# Adafruit_PowerBoost_1000C.net
KiCad netlist of a schematic drawn in EAGLE
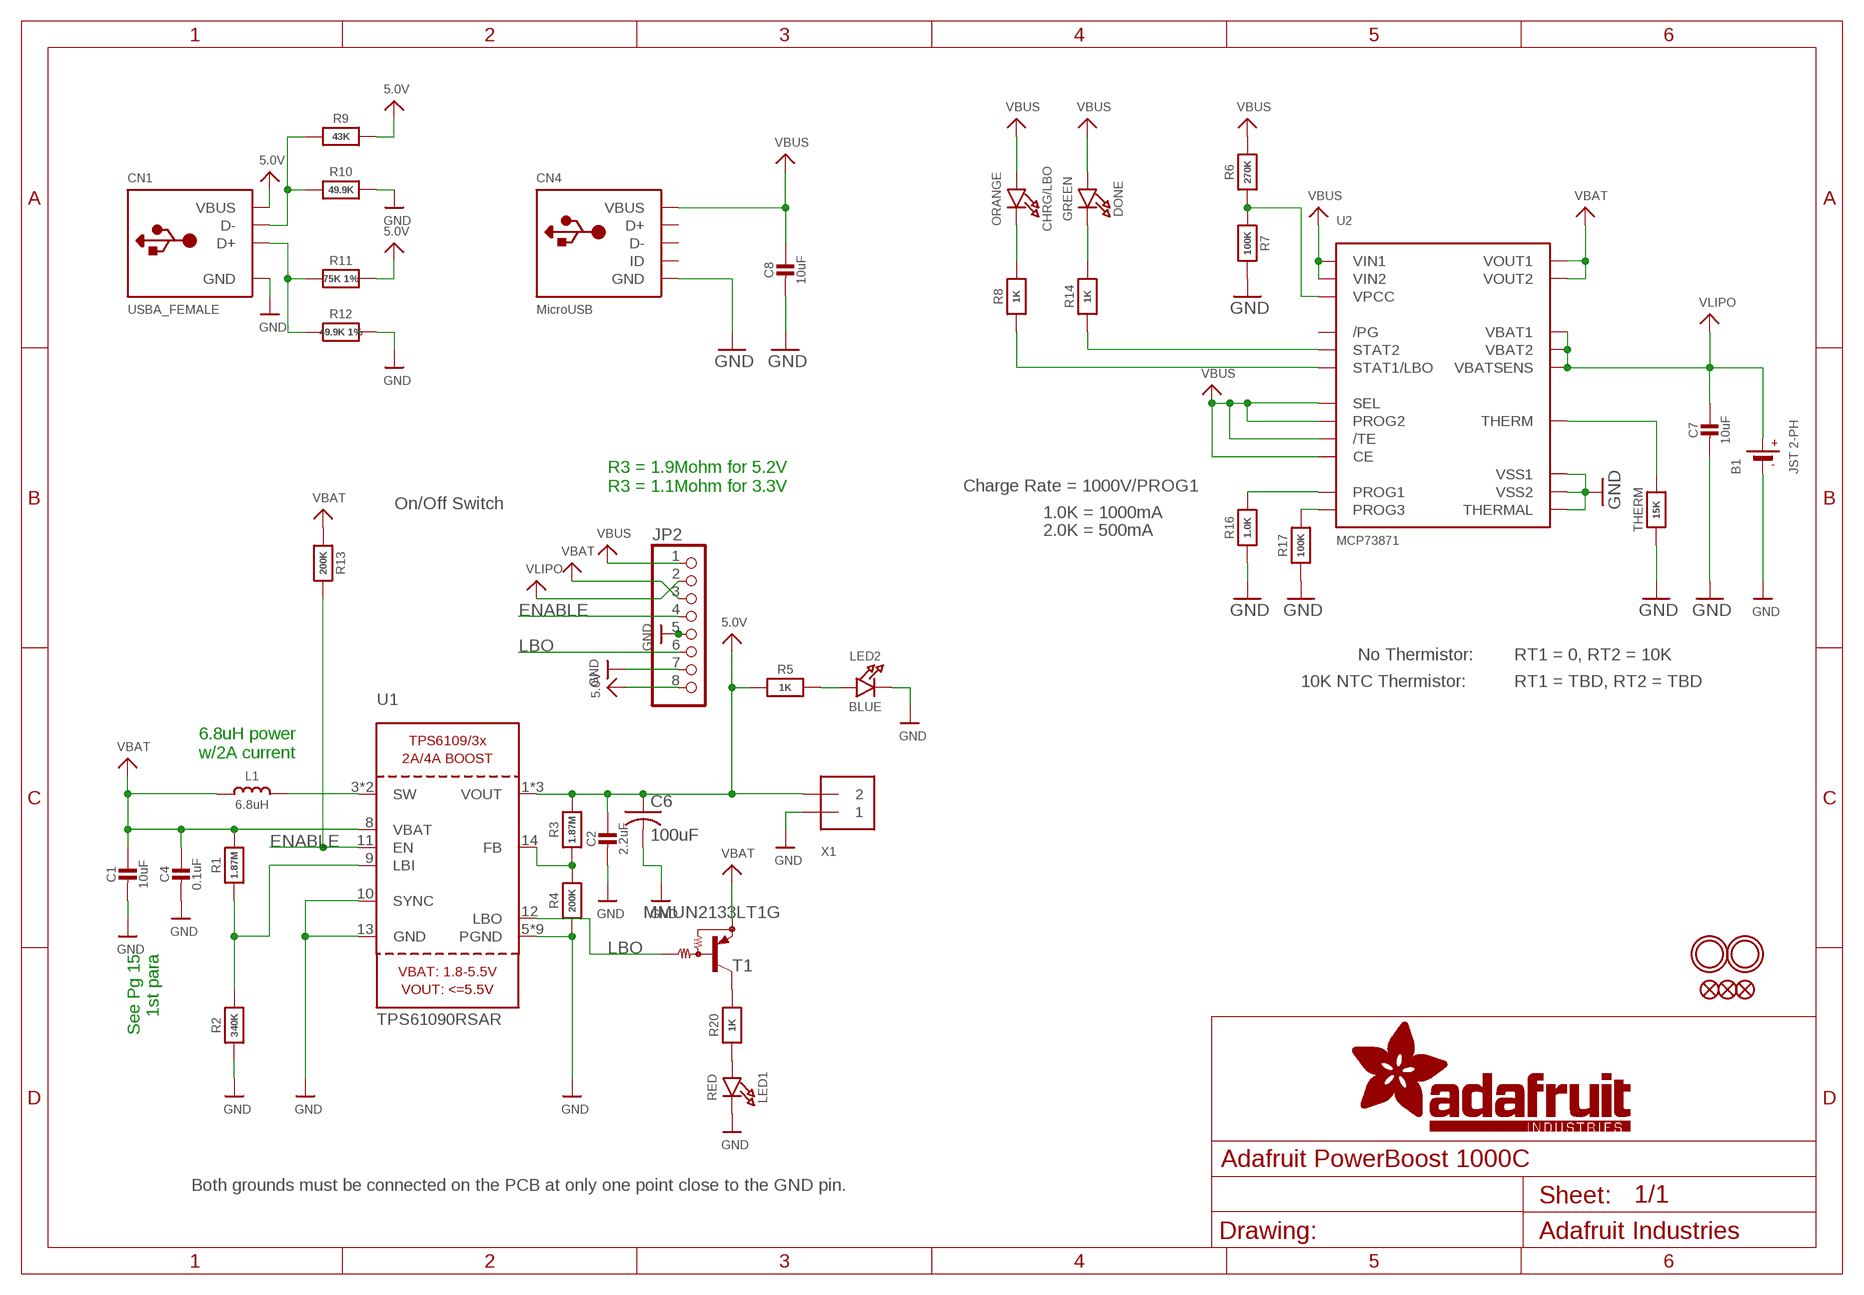
[diagram p0: schematic, sheet 1]

(export (version "E")
  (design (tool "Eeschema 10.0.6"))
  (components
    (comp (ref "B1")
      (value "JST 2-PH")
      (footprint "eagle-import:JSTPH2")
      (libsource (lib "eagle-import") (part "BATTERY"))
    )
    (comp (ref "C1")
      (value "10uF")
      (footprint "eagle-import:0805-NO")
      (libsource (lib "eagle-import") (part "CAP_CERAMIC0805-NOOUTLINE"))
    )
    (comp (ref "C2")
      (value "2.2uF")
      (footprint "eagle-import:0805-NO")
      (libsource (lib "eagle-import") (part "CAP_CERAMIC0805-NOOUTLINE"))
    )
    (comp (ref "C4")
      (value "0.1uF")
      (footprint "eagle-import:0805_10MGAP")
      (libsource (lib "eagle-import") (part "CAP_CERAMIC0805_10MGAP"))
    )
    (comp (ref "C6")
      (value "100uF")
      (footprint "eagle-import:C1210")
      (libsource (lib "eagle-import") (part "C-USC1210"))
    )
    (comp (ref "C7")
      (value "10uF")
      (footprint "eagle-import:0805-NO")
      (libsource (lib "eagle-import") (part "CAP_CERAMIC0805-NOOUTLINE"))
    )
    (comp (ref "C8")
      (value "10uF")
      (footprint "eagle-import:0805-NO")
      (libsource (lib "eagle-import") (part "CAP_CERAMIC0805-NOOUTLINE"))
    )
    (comp (ref "CHRG/LBO")
      (value "ORANGE")
      (footprint "eagle-import:CHIPLED_0805_NOOUTLINE")
      (libsource (lib "eagle-import") (part "LED0805_NOOUTLINE"))
    )
    (comp (ref "CN1")
      (value "USBA_FEMALE")
      (footprint "eagle-import:USB_HOST-PTH")
      (libsource (lib "eagle-import") (part "USB_TYPEAPTHFML"))
    )
    (comp (ref "CN4")
      (value "MicroUSB")
      (footprint "eagle-import:4UCONN_20329")
      (libsource (lib "eagle-import") (part "USBMICRO_20329"))
    )
    (comp (ref "DONE")
      (value "GREEN")
      (footprint "eagle-import:CHIPLED_0805_NOOUTLINE")
      (libsource (lib "eagle-import") (part "LED0805_NOOUTLINE"))
    )
    (comp (ref "FID1")
      (value "FIDUCIAL\"\"")
      (footprint "eagle-import:FIDUCIAL_1MM")
      (fields (field (name "BOM") "EXCLUDE"))
      (libsource (lib "eagle-import") (part "FIDUCIAL{dblquote}{dblquote}"))
    )
    (comp (ref "FID2")
      (value "FIDUCIAL\"\"")
      (footprint "eagle-import:FIDUCIAL_1MM")
      (libsource (lib "eagle-import") (part "FIDUCIAL{dblquote}{dblquote}"))
    )
    (comp (ref "FID3")
      (value "FIDUCIAL\"\"")
      (footprint "eagle-import:FIDUCIAL_1MM")
      (fields (field (name "BOM") "EXCLUDE"))
      (libsource (lib "eagle-import") (part "FIDUCIAL{dblquote}{dblquote}"))
    )
    (comp (ref "JP2")
      (value "HEADER-1X8ROUND")
      (footprint "eagle-import:1X08_ROUND")
      (libsource (lib "eagle-import") (part "HEADER-1X8ROUND"))
    )
    (comp (ref "L1")
      (value "6.8uH")
      (footprint "eagle-import:INDUCTOR_5X5MM_TDK_VLC5045")
      (libsource (lib "eagle-import") (part "INDUCTORTDK_VLC5045"))
    )
    (comp (ref "LED1")
      (value "RED")
      (footprint "eagle-import:CHIPLED_0805_NOOUTLINE")
      (libsource (lib "eagle-import") (part "LED0805_NOOUTLINE"))
    )
    (comp (ref "LED2")
      (value "BLUE")
      (footprint "eagle-import:CHIPLED_0805_NOOUTLINE")
      (libsource (lib "eagle-import") (part "LED0805_NOOUTLINE"))
    )
    (comp (ref "R1")
      (value "1.87M")
      (footprint "eagle-import:_0805MP")
      (libsource (lib "eagle-import") (part "RESISTOR_0805MP"))
    )
    (comp (ref "R2")
      (value "340K")
      (footprint "eagle-import:_0805MP")
      (libsource (lib "eagle-import") (part "RESISTOR_0805MP"))
    )
    (comp (ref "R3")
      (value "1.87M")
      (footprint "eagle-import:0805-NO")
      (libsource (lib "eagle-import") (part "RESISTOR0805_NOOUTLINE"))
    )
    (comp (ref "R4")
      (value "200K")
      (footprint "eagle-import:0805-NO")
      (libsource (lib "eagle-import") (part "RESISTOR0805_NOOUTLINE"))
    )
    (comp (ref "R5")
      (value "1K")
      (footprint "eagle-import:0805-NO")
      (libsource (lib "eagle-import") (part "RESISTOR0805_NOOUTLINE"))
    )
    (comp (ref "R6")
      (value "270K")
      (footprint "eagle-import:0805-NO")
      (libsource (lib "eagle-import") (part "RESISTOR0805_NOOUTLINE"))
    )
    (comp (ref "R7")
      (value "100K")
      (footprint "eagle-import:0805-NO")
      (libsource (lib "eagle-import") (part "RESISTOR0805_NOOUTLINE"))
    )
    (comp (ref "R8")
      (value "1K")
      (footprint "eagle-import:0805-NO")
      (libsource (lib "eagle-import") (part "RESISTOR0805_NOOUTLINE"))
    )
    (comp (ref "R9")
      (value "43K")
      (footprint "eagle-import:0805-NO")
      (libsource (lib "eagle-import") (part "RESISTOR0805_NOOUTLINE"))
    )
    (comp (ref "R10")
      (value "49.9K")
      (footprint "eagle-import:0805-NO")
      (libsource (lib "eagle-import") (part "RESISTOR0805_NOOUTLINE"))
    )
    (comp (ref "R11")
      (value "75K 1%")
      (footprint "eagle-import:0805-NO")
      (libsource (lib "eagle-import") (part "RESISTOR0805_NOOUTLINE"))
    )
    (comp (ref "R12")
      (value "49.9K 1%")
      (footprint "eagle-import:0805-NO")
      (libsource (lib "eagle-import") (part "RESISTOR0805_NOOUTLINE"))
    )
    (comp (ref "R13")
      (value "200K")
      (footprint "eagle-import:0805-NO")
      (libsource (lib "eagle-import") (part "RESISTOR0805_NOOUTLINE"))
    )
    (comp (ref "R14")
      (value "1K")
      (footprint "eagle-import:0805-NO")
      (libsource (lib "eagle-import") (part "RESISTOR0805_NOOUTLINE"))
    )
    (comp (ref "R16")
      (value "1.0K")
      (footprint "eagle-import:0805-NO")
      (libsource (lib "eagle-import") (part "RESISTOR0805_NOOUTLINE"))
    )
    (comp (ref "R17")
      (value "100K")
      (footprint "eagle-import:0805-NO")
      (libsource (lib "eagle-import") (part "RESISTOR0805_NOOUTLINE"))
    )
    (comp (ref "R20")
      (value "1K")
      (footprint "eagle-import:0805-NO")
      (libsource (lib "eagle-import") (part "RESISTOR0805_NOOUTLINE"))
    )
    (comp (ref "T1")
      (value "MMUN2133LT1G")
      (footprint "eagle-import:SC59-BEC")
      (libsource (lib "eagle-import") (part "-PNP_DRIVER-SC59-BECMUN2114T1"))
    )
    (comp (ref "THERM")
      (value "15K")
      (footprint "eagle-import:0805-NO")
      (libsource (lib "eagle-import") (part "RESISTOR0805_NOOUTLINE"))
    )
    (comp (ref "U$10")
      (value "MOUNTINGHOLE2.5")
      (footprint "eagle-import:MOUNTINGHOLE_2.5_PLATED")
      (libsource (lib "eagle-import") (part "MOUNTINGHOLE2.5"))
    )
    (comp (ref "U$11")
      (value "MOUNTINGHOLE2.5")
      (footprint "eagle-import:MOUNTINGHOLE_2.5_PLATED")
      (libsource (lib "eagle-import") (part "MOUNTINGHOLE2.5"))
    )
    (comp (ref "U1")
      (value "TPS61090RSAR")
      (footprint "eagle-import:PVQFN-16")
      (libsource (lib "eagle-import") (part "VREG_TPS6103X"))
    )
    (comp (ref "U2")
      (value "MCP73871")
      (footprint "eagle-import:QFN20_4MM")
      (libsource (lib "eagle-import") (part "MCP73871"))
    )
    (comp (ref "X1")
      (value "TERMBLOCK_1X2")
      (footprint "eagle-import:TERMBLOCK_1X2-3.5MM")
      (libsource (lib "eagle-import") (part "TERMBLOCK_1X2"))
    )
  )
  (nets
    (net (code "1") (name "/ENABLE") (class "Default")
      (node (ref "JP2") (pin "4") (pinfunction "4_4") (pintype "passive"))
      (node (ref "R13") (pin "2") (pinfunction "2_2") (pintype "passive"))
      (node (ref "U1") (pin "11") (pinfunction "EN_11") (pintype "input"))
    )
    (net (code "2") (name "/LBO") (class "Default")
      (node (ref "JP2") (pin "6") (pinfunction "6_6") (pintype "passive"))
      (node (ref "T1") (pin "B") (pinfunction "B_B") (pintype "passive"))
      (node (ref "U1") (pin "12") (pinfunction "LBO_12") (pintype "output"))
    )
    (net (code "3") (name "5.0V") (class "Default")
      (node (ref "C2") (pin "1") (pinfunction "1_1") (pintype "passive"))
      (node (ref "C6") (pin "1") (pinfunction "1_1") (pintype "passive"))
      (node (ref "CN1") (pin "VBUS") (pinfunction "VBUS_VBUS") (pintype "power_in"))
      (node (ref "JP2") (pin "8") (pinfunction "8_8") (pintype "passive"))
      (node (ref "R11") (pin "2") (pinfunction "2_2") (pintype "passive"))
      (node (ref "R3") (pin "2") (pinfunction "2_2") (pintype "passive"))
      (node (ref "R5") (pin "1") (pinfunction "1_1") (pintype "passive"))
      (node (ref "R9") (pin "2") (pinfunction "2_2") (pintype "passive"))
      (node (ref "U1") (pin "1") (pinfunction "VOUT_1") (pintype "power_in"))
      (node (ref "U1") (pin "15") (pinfunction "VOUT_15") (pintype "power_in"))
      (node (ref "U1") (pin "16") (pinfunction "VOUT_16") (pintype "power_in"))
      (node (ref "X1") (pin "2") (pinfunction "2_2") (pintype "passive"))
    )
    (net (code "4") (name "GND") (class "Default")
      (node (ref "B1") (pin "1") (pinfunction "-_1") (pintype "passive"))
      (node (ref "C1") (pin "2") (pinfunction "2_2") (pintype "passive"))
      (node (ref "C2") (pin "2") (pinfunction "2_2") (pintype "passive"))
      (node (ref "C4") (pin "2") (pinfunction "2_2") (pintype "passive"))
      (node (ref "C6") (pin "2") (pinfunction "2_2") (pintype "passive"))
      (node (ref "C7") (pin "2") (pinfunction "2_2") (pintype "passive"))
      (node (ref "C8") (pin "2") (pinfunction "2_2") (pintype "passive"))
      (node (ref "CN1") (pin "GND") (pinfunction "GND_GND") (pintype "power_in"))
      (node (ref "CN4") (pin "BASE@1") (pinfunction "GND_BASE@1") (pintype "power_in"))
      (node (ref "CN4") (pin "BASE@2") (pinfunction "GND_BASE@2") (pintype "power_in"))
      (node (ref "CN4") (pin "GND") (pinfunction "GND_GND") (pintype "power_in"))
      (node (ref "CN4") (pin "SPRT@1") (pinfunction "GND_SPRT@1") (pintype "power_in"))
      (node (ref "CN4") (pin "SPRT@2") (pinfunction "GND_SPRT@2") (pintype "power_in"))
      (node (ref "CN4") (pin "SPRT@3") (pinfunction "GND_SPRT@3") (pintype "power_in"))
      (node (ref "CN4") (pin "SPRT@4") (pinfunction "GND_SPRT@4") (pintype "power_in"))
      (node (ref "JP2") (pin "5") (pinfunction "5_5") (pintype "passive"))
      (node (ref "JP2") (pin "7") (pinfunction "7_7") (pintype "passive"))
      (node (ref "LED1") (pin "C") (pinfunction "C_C") (pintype "passive"))
      (node (ref "LED2") (pin "C") (pinfunction "C_C") (pintype "passive"))
      (node (ref "R10") (pin "2") (pinfunction "2_2") (pintype "passive"))
      (node (ref "R12") (pin "2") (pinfunction "2_2") (pintype "passive"))
      (node (ref "R16") (pin "1") (pinfunction "1_1") (pintype "passive"))
      (node (ref "R17") (pin "1") (pinfunction "1_1") (pintype "passive"))
      (node (ref "R2") (pin "1") (pinfunction "1_1") (pintype "passive"))
      (node (ref "R4") (pin "1") (pinfunction "1_1") (pintype "passive"))
      (node (ref "R7") (pin "2") (pinfunction "2_2") (pintype "passive"))
      (node (ref "THERM") (pin "1") (pinfunction "1_1") (pintype "passive"))
      (node (ref "U1") (pin "10") (pinfunction "SYNC_10") (pintype "input"))
      (node (ref "U1") (pin "13") (pinfunction "GND_13") (pintype "power_in"))
      (node (ref "U1") (pin "5") (pinfunction "PGND_5") (pintype "power_in"))
      (node (ref "U1") (pin "6") (pinfunction "PGND_6") (pintype "power_in"))
      (node (ref "U1") (pin "7") (pinfunction "PGND_7") (pintype "power_in"))
      (node (ref "U1") (pin "P$18") (pinfunction "PGND_P$18") (pintype "power_in"))
      (node (ref "U1") (pin "P$19") (pinfunction "PGND_P$19") (pintype "power_in"))
      (node (ref "U1") (pin "P$20") (pinfunction "PGND_P$20") (pintype "power_in"))
      (node (ref "U1") (pin "P$21") (pinfunction "PGND_P$21") (pintype "power_in"))
      (node (ref "U1") (pin "P$22") (pinfunction "PGND_P$22") (pintype "power_in"))
      (node (ref "U1") (pin "THERMAL") (pinfunction "PGND_THERMAL") (pintype "power_in"))
      (node (ref "U2") (pin "P$10") (pinfunction "VSS1_P$10") (pintype "bidirectional"))
      (node (ref "U2") (pin "P$11") (pinfunction "VSS2_P$11") (pintype "bidirectional"))
      (node (ref "U2") (pin "P$21") (pinfunction "THERMAL_P$21") (pintype "bidirectional"))
      (node (ref "X1") (pin "1") (pinfunction "1_1") (pintype "passive"))
    )
    (net (code "5") (name "Net-(CHRG/LBO-PadC)") (class "Default")
      (node (ref "CHRG/LBO") (pin "C") (pinfunction "C_C") (pintype "passive"))
      (node (ref "R8") (pin "2") (pinfunction "2_2") (pintype "passive"))
    )
    (net (code "6") (name "Net-(CN1-PadD+)") (class "Default")
      (node (ref "CN1") (pin "D+") (pinfunction "D+_D+") (pintype "bidirectional"))
      (node (ref "R11") (pin "1") (pinfunction "1_1") (pintype "passive"))
      (node (ref "R12") (pin "1") (pinfunction "1_1") (pintype "passive"))
    )
    (net (code "7") (name "Net-(CN1-PadD-)") (class "Default")
      (node (ref "CN1") (pin "D-") (pinfunction "D-_D-") (pintype "bidirectional"))
      (node (ref "R10") (pin "1") (pinfunction "1_1") (pintype "passive"))
      (node (ref "R9") (pin "1") (pinfunction "1_1") (pintype "passive"))
    )
    (net (code "8") (name "Net-(DONE-PadC)") (class "Default")
      (node (ref "DONE") (pin "C") (pinfunction "C_C") (pintype "passive"))
      (node (ref "R14") (pin "2") (pinfunction "2_2") (pintype "passive"))
    )
    (net (code "9") (name "Net-(L1-2)") (class "Default")
      (node (ref "L1") (pin "P$2") (pinfunction "2_P$2") (pintype "passive"))
      (node (ref "U1") (pin "3") (pinfunction "SW_3") (pintype "input"))
      (node (ref "U1") (pin "4") (pinfunction "SW_4") (pintype "input"))
    )
    (net (code "10") (name "Net-(LED1-PadA)") (class "Default")
      (node (ref "LED1") (pin "A") (pinfunction "A_A") (pintype "passive"))
      (node (ref "R20") (pin "1") (pinfunction "1_1") (pintype "passive"))
    )
    (net (code "11") (name "Net-(LED2-PadA)") (class "Default")
      (node (ref "LED2") (pin "A") (pinfunction "A_A") (pintype "passive"))
      (node (ref "R5") (pin "2") (pinfunction "2_2") (pintype "passive"))
    )
    (net (code "12") (name "Net-(R20-Pad2)") (class "Default")
      (node (ref "R20") (pin "2") (pinfunction "2_2") (pintype "passive"))
      (node (ref "T1") (pin "C") (pinfunction "C_C") (pintype "passive"))
    )
    (net (code "13") (name "Net-(U1-FB)") (class "Default")
      (node (ref "R3") (pin "1") (pinfunction "1_1") (pintype "passive"))
      (node (ref "R4") (pin "2") (pinfunction "2_2") (pintype "passive"))
      (node (ref "U1") (pin "14") (pinfunction "FB_14") (pintype "input"))
    )
    (net (code "14") (name "Net-(U1-LBI)") (class "Default")
      (node (ref "R1") (pin "1") (pinfunction "1_1") (pintype "passive"))
      (node (ref "R2") (pin "2") (pinfunction "2_2") (pintype "passive"))
      (node (ref "U1") (pin "9") (pinfunction "LBI_9") (pintype "input"))
    )
    (net (code "15") (name "Net-(U2-PROG1)") (class "Default")
      (node (ref "R16") (pin "2") (pinfunction "2_2") (pintype "passive"))
      (node (ref "U2") (pin "P$13") (pinfunction "PROG1_P$13") (pintype "bidirectional"))
    )
    (net (code "16") (name "Net-(U2-PROG3)") (class "Default")
      (node (ref "R17") (pin "2") (pinfunction "2_2") (pintype "passive"))
      (node (ref "U2") (pin "P$12") (pinfunction "PROG3_P$12") (pintype "bidirectional"))
    )
    (net (code "17") (name "Net-(U2-STAT1{slash}LBO)") (class "Default")
      (node (ref "R8") (pin "1") (pinfunction "1_1") (pintype "passive"))
      (node (ref "U2") (pin "P$8") (pinfunction "STAT1/LBO_P$8") (pintype "bidirectional"))
    )
    (net (code "18") (name "Net-(U2-STAT2)") (class "Default")
      (node (ref "R14") (pin "1") (pinfunction "1_1") (pintype "passive"))
      (node (ref "U2") (pin "P$7") (pinfunction "STAT2_P$7") (pintype "bidirectional"))
    )
    (net (code "19") (name "Net-(U2-THERM)") (class "Default")
      (node (ref "THERM") (pin "2") (pinfunction "2_2") (pintype "passive"))
      (node (ref "U2") (pin "P$5") (pinfunction "THERM_P$5") (pintype "bidirectional"))
    )
    (net (code "20") (name "Net-(U2-VPCC)") (class "Default")
      (node (ref "R6") (pin "1") (pinfunction "1_1") (pintype "passive"))
      (node (ref "R7") (pin "1") (pinfunction "1_1") (pintype "passive"))
      (node (ref "U2") (pin "P$2") (pinfunction "VPCC_P$2") (pintype "bidirectional"))
    )
    (net (code "21") (name "VBAT") (class "Default")
      (node (ref "C1") (pin "1") (pinfunction "1_1") (pintype "passive"))
      (node (ref "C4") (pin "1") (pinfunction "1_1") (pintype "passive"))
      (node (ref "JP2") (pin "3") (pinfunction "3_3") (pintype "passive"))
      (node (ref "L1") (pin "P$1") (pinfunction "1_P$1") (pintype "passive"))
      (node (ref "R1") (pin "2") (pinfunction "2_2") (pintype "passive"))
      (node (ref "R13") (pin "1") (pinfunction "1_1") (pintype "passive"))
      (node (ref "T1") (pin "E") (pinfunction "E_E") (pintype "passive"))
      (node (ref "U1") (pin "8") (pinfunction "VBAT_8") (pintype "input"))
      (node (ref "U2") (pin "P$1") (pinfunction "VOUT1_P$1") (pintype "bidirectional"))
      (node (ref "U2") (pin "P$20") (pinfunction "VOUT2_P$20") (pintype "bidirectional"))
    )
    (net (code "22") (name "VBUS") (class "Default")
      (node (ref "C8") (pin "1") (pinfunction "1_1") (pintype "passive"))
      (node (ref "CHRG/LBO") (pin "A") (pinfunction "A_A") (pintype "passive"))
      (node (ref "CN4") (pin "VBUS") (pinfunction "VBUS_VBUS") (pintype "power_in"))
      (node (ref "DONE") (pin "A") (pinfunction "A_A") (pintype "passive"))
      (node (ref "JP2") (pin "1") (pinfunction "1_1") (pintype "passive"))
      (node (ref "R6") (pin "2") (pinfunction "2_2") (pintype "passive"))
      (node (ref "U2") (pin "P$17") (pinfunction "CE_P$17") (pintype "bidirectional"))
      (node (ref "U2") (pin "P$18") (pinfunction "VIN1_P$18") (pintype "bidirectional"))
      (node (ref "U2") (pin "P$19") (pinfunction "VIN2_P$19") (pintype "bidirectional"))
      (node (ref "U2") (pin "P$3") (pinfunction "SEL_P$3") (pintype "bidirectional"))
      (node (ref "U2") (pin "P$4") (pinfunction "PROG2_P$4") (pintype "bidirectional"))
      (node (ref "U2") (pin "P$9") (pinfunction "/TE_P$9") (pintype "bidirectional"))
    )
    (net (code "23") (name "VLIPO") (class "Default")
      (node (ref "B1") (pin "2") (pinfunction "+_2") (pintype "passive"))
      (node (ref "C7") (pin "1") (pinfunction "1_1") (pintype "passive"))
      (node (ref "JP2") (pin "2") (pinfunction "2_2") (pintype "passive"))
      (node (ref "U2") (pin "P$14") (pinfunction "VBAT1_P$14") (pintype "bidirectional"))
      (node (ref "U2") (pin "P$15") (pinfunction "VBAT2_P$15") (pintype "bidirectional"))
      (node (ref "U2") (pin "P$16") (pinfunction "VBATSENS_P$16") (pintype "bidirectional"))
    )
    (net (code "24") (name "unconnected-(CN4-PadD+)") (class "Default")
      (node (ref "CN4") (pin "D+") (pinfunction "D+_D+") (pintype "bidirectional"))
    )
    (net (code "25") (name "unconnected-(CN4-PadD-)") (class "Default")
      (node (ref "CN4") (pin "D-") (pinfunction "D-_D-") (pintype "bidirectional"))
    )
    (net (code "26") (name "unconnected-(CN4-PadID)") (class "Default")
      (node (ref "CN4") (pin "ID") (pinfunction "ID_ID") (pintype "bidirectional"))
    )
    (net (code "27") (name "unconnected-(U2-{slash}PG-PadP$6)") (class "Default")
      (node (ref "U2") (pin "P$6") (pinfunction "/PG_P$6") (pintype "bidirectional"))
    )
  )
)
